# UnitB.net
KiCad netlist of a schematic drawn in Altium Designer
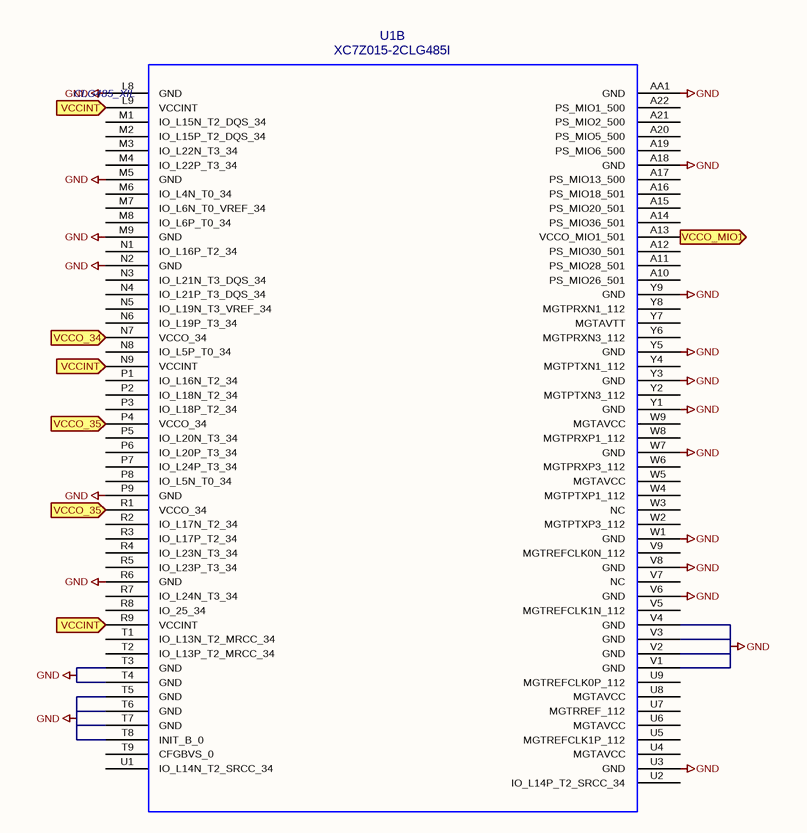
[diagram p0: UnitB.SchDoc]

(export (version "E")
  (design (tool "Eeschema 10.0.6"))
  (components
    (comp (ref "U1")
      (value "XC7Z015-2CLG485I")
      (footprint "CLG485_XIL")
      (libsource (lib "XC7Z015-CLG485") (part "XC7Z015-2CLG485I"))
    )
  )
  (nets
    (net (code "1") (name "/VCCINT") (class "Default")
      (node (ref "U1") (pin "L9") (pinfunction "VCCINT_L9") (pintype "passive"))
      (node (ref "U1") (pin "N9") (pinfunction "VCCINT_N9") (pintype "passive"))
      (node (ref "U1") (pin "R9") (pinfunction "VCCINT_R9") (pintype "passive"))
    )
    (net (code "2") (name "/VCCO_34") (class "Default")
      (node (ref "U1") (pin "N7") (pinfunction "VCCO_34_N7") (pintype "passive"))
    )
    (net (code "3") (name "/VCCO_35") (class "Default")
      (node (ref "U1") (pin "P4") (pinfunction "VCCO_34_P4") (pintype "passive"))
      (node (ref "U1") (pin "R1") (pinfunction "VCCO_34_R1") (pintype "passive"))
    )
    (net (code "4") (name "/VCCO_MIO1") (class "Default")
      (node (ref "U1") (pin "A13") (pinfunction "VCCO_MIO1_501_A13") (pintype "passive"))
    )
    (net (code "5") (name "GND") (class "Default")
      (node (ref "U1") (pin "A18") (pinfunction "GND_A18") (pintype "passive"))
      (node (ref "U1") (pin "AA1") (pinfunction "GND_AA1") (pintype "passive"))
      (node (ref "U1") (pin "L8") (pinfunction "GND_L8") (pintype "passive"))
      (node (ref "U1") (pin "M5") (pinfunction "GND_M5") (pintype "passive"))
      (node (ref "U1") (pin "M9") (pinfunction "GND_M9") (pintype "passive"))
      (node (ref "U1") (pin "N2") (pinfunction "GND_N2") (pintype "passive"))
      (node (ref "U1") (pin "P9") (pinfunction "GND_P9") (pintype "passive"))
      (node (ref "U1") (pin "R6") (pinfunction "GND_R6") (pintype "passive"))
      (node (ref "U1") (pin "T3") (pinfunction "GND_T3") (pintype "passive"))
      (node (ref "U1") (pin "T4") (pinfunction "GND_T4") (pintype "passive"))
      (node (ref "U1") (pin "T5") (pinfunction "GND_T5") (pintype "passive"))
      (node (ref "U1") (pin "T6") (pinfunction "GND_T6") (pintype "passive"))
      (node (ref "U1") (pin "T7") (pinfunction "GND_T7") (pintype "passive"))
      (node (ref "U1") (pin "T8") (pinfunction "INIT_B_0_T8") (pintype "passive"))
      (node (ref "U1") (pin "U3") (pinfunction "GND_U3") (pintype "passive"))
      (node (ref "U1") (pin "V1") (pinfunction "GND_V1") (pintype "passive"))
      (node (ref "U1") (pin "V2") (pinfunction "GND_V2") (pintype "passive"))
      (node (ref "U1") (pin "V3") (pinfunction "GND_V3") (pintype "passive"))
      (node (ref "U1") (pin "V4") (pinfunction "GND_V4") (pintype "passive"))
      (node (ref "U1") (pin "V6") (pinfunction "GND_V6") (pintype "passive"))
      (node (ref "U1") (pin "V8") (pinfunction "GND_V8") (pintype "passive"))
      (node (ref "U1") (pin "W1") (pinfunction "GND_W1") (pintype "passive"))
      (node (ref "U1") (pin "W7") (pinfunction "GND_W7") (pintype "passive"))
      (node (ref "U1") (pin "Y1") (pinfunction "GND_Y1") (pintype "passive"))
      (node (ref "U1") (pin "Y3") (pinfunction "GND_Y3") (pintype "passive"))
      (node (ref "U1") (pin "Y5") (pinfunction "GND_Y5") (pintype "passive"))
      (node (ref "U1") (pin "Y9") (pinfunction "GND_Y9") (pintype "passive"))
    )
    (net (code "6") (name "unconnected-(U1B-CFGBVS_0-PadT9)") (class "Default")
      (node (ref "U1") (pin "T9") (pinfunction "CFGBVS_0_T9") (pintype "passive"))
    )
    (net (code "7") (name "unconnected-(U1B-IO_25_34-PadR8)") (class "Default")
      (node (ref "U1") (pin "R8") (pinfunction "IO_25_34_R8") (pintype "passive"))
    )
    (net (code "8") (name "unconnected-(U1B-IO_L4N_T0_34-PadM6)") (class "Default")
      (node (ref "U1") (pin "M6") (pinfunction "IO_L4N_T0_34_M6") (pintype "passive"))
    )
    (net (code "9") (name "unconnected-(U1B-IO_L5N_T0_34-PadP8)") (class "Default")
      (node (ref "U1") (pin "P8") (pinfunction "IO_L5N_T0_34_P8") (pintype "passive"))
    )
    (net (code "10") (name "unconnected-(U1B-IO_L5P_T0_34-PadN8)") (class "Default")
      (node (ref "U1") (pin "N8") (pinfunction "IO_L5P_T0_34_N8") (pintype "passive"))
    )
    (net (code "11") (name "unconnected-(U1B-IO_L6N_T0_VREF_34-PadM7)") (class "Default")
      (node (ref "U1") (pin "M7") (pinfunction "IO_L6N_T0_VREF_34_M7") (pintype "passive"))
    )
    (net (code "12") (name "unconnected-(U1B-IO_L6P_T0_34-PadM8)") (class "Default")
      (node (ref "U1") (pin "M8") (pinfunction "IO_L6P_T0_34_M8") (pintype "passive"))
    )
    (net (code "13") (name "unconnected-(U1B-IO_L13N_T2_MRCC_34-PadT1)") (class "Default")
      (node (ref "U1") (pin "T1") (pinfunction "IO_L13N_T2_MRCC_34_T1") (pintype "passive"))
    )
    (net (code "14") (name "unconnected-(U1B-IO_L13P_T2_MRCC_34-PadT2)") (class "Default")
      (node (ref "U1") (pin "T2") (pinfunction "IO_L13P_T2_MRCC_34_T2") (pintype "passive"))
    )
    (net (code "15") (name "unconnected-(U1B-IO_L14N_T2_SRCC_34-PadU1)") (class "Default")
      (node (ref "U1") (pin "U1") (pinfunction "IO_L14N_T2_SRCC_34_U1") (pintype "passive"))
    )
    (net (code "16") (name "unconnected-(U1B-IO_L14P_T2_SRCC_34-PadU2)") (class "Default")
      (node (ref "U1") (pin "U2") (pinfunction "IO_L14P_T2_SRCC_34_U2") (pintype "passive"))
    )
    (net (code "17") (name "unconnected-(U1B-IO_L15N_T2_DQS_34-PadM1)") (class "Default")
      (node (ref "U1") (pin "M1") (pinfunction "IO_L15N_T2_DQS_34_M1") (pintype "passive"))
    )
    (net (code "18") (name "unconnected-(U1B-IO_L15P_T2_DQS_34-PadM2)") (class "Default")
      (node (ref "U1") (pin "M2") (pinfunction "IO_L15P_T2_DQS_34_M2") (pintype "passive"))
    )
    (net (code "19") (name "unconnected-(U1B-IO_L16N_T2_34-PadP1)") (class "Default")
      (node (ref "U1") (pin "P1") (pinfunction "IO_L16N_T2_34_P1") (pintype "passive"))
    )
    (net (code "20") (name "unconnected-(U1B-IO_L16P_T2_34-PadN1)") (class "Default")
      (node (ref "U1") (pin "N1") (pinfunction "IO_L16P_T2_34_N1") (pintype "passive"))
    )
    (net (code "21") (name "unconnected-(U1B-IO_L17N_T2_34-PadR2)") (class "Default")
      (node (ref "U1") (pin "R2") (pinfunction "IO_L17N_T2_34_R2") (pintype "passive"))
    )
    (net (code "22") (name "unconnected-(U1B-IO_L17P_T2_34-PadR3)") (class "Default")
      (node (ref "U1") (pin "R3") (pinfunction "IO_L17P_T2_34_R3") (pintype "passive"))
    )
    (net (code "23") (name "unconnected-(U1B-IO_L18N_T2_34-PadP2)") (class "Default")
      (node (ref "U1") (pin "P2") (pinfunction "IO_L18N_T2_34_P2") (pintype "passive"))
    )
    (net (code "24") (name "unconnected-(U1B-IO_L18P_T2_34-PadP3)") (class "Default")
      (node (ref "U1") (pin "P3") (pinfunction "IO_L18P_T2_34_P3") (pintype "passive"))
    )
    (net (code "25") (name "unconnected-(U1B-IO_L19N_T3_VREF_34-PadN5)") (class "Default")
      (node (ref "U1") (pin "N5") (pinfunction "IO_L19N_T3_VREF_34_N5") (pintype "passive"))
    )
    (net (code "26") (name "unconnected-(U1B-IO_L19P_T3_34-PadN6)") (class "Default")
      (node (ref "U1") (pin "N6") (pinfunction "IO_L19P_T3_34_N6") (pintype "passive"))
    )
    (net (code "27") (name "unconnected-(U1B-IO_L20N_T3_34-PadP5)") (class "Default")
      (node (ref "U1") (pin "P5") (pinfunction "IO_L20N_T3_34_P5") (pintype "passive"))
    )
    (net (code "28") (name "unconnected-(U1B-IO_L20P_T3_34-PadP6)") (class "Default")
      (node (ref "U1") (pin "P6") (pinfunction "IO_L20P_T3_34_P6") (pintype "passive"))
    )
    (net (code "29") (name "unconnected-(U1B-IO_L21N_T3_DQS_34-PadN3)") (class "Default")
      (node (ref "U1") (pin "N3") (pinfunction "IO_L21N_T3_DQS_34_N3") (pintype "passive"))
    )
    (net (code "30") (name "unconnected-(U1B-IO_L21P_T3_DQS_34-PadN4)") (class "Default")
      (node (ref "U1") (pin "N4") (pinfunction "IO_L21P_T3_DQS_34_N4") (pintype "passive"))
    )
    (net (code "31") (name "unconnected-(U1B-IO_L22N_T3_34-PadM3)") (class "Default")
      (node (ref "U1") (pin "M3") (pinfunction "IO_L22N_T3_34_M3") (pintype "passive"))
    )
    (net (code "32") (name "unconnected-(U1B-IO_L22P_T3_34-PadM4)") (class "Default")
      (node (ref "U1") (pin "M4") (pinfunction "IO_L22P_T3_34_M4") (pintype "passive"))
    )
    (net (code "33") (name "unconnected-(U1B-IO_L23N_T3_34-PadR4)") (class "Default")
      (node (ref "U1") (pin "R4") (pinfunction "IO_L23N_T3_34_R4") (pintype "passive"))
    )
    (net (code "34") (name "unconnected-(U1B-IO_L23P_T3_34-PadR5)") (class "Default")
      (node (ref "U1") (pin "R5") (pinfunction "IO_L23P_T3_34_R5") (pintype "passive"))
    )
    (net (code "35") (name "unconnected-(U1B-IO_L24N_T3_34-PadR7)") (class "Default")
      (node (ref "U1") (pin "R7") (pinfunction "IO_L24N_T3_34_R7") (pintype "passive"))
    )
    (net (code "36") (name "unconnected-(U1B-IO_L24P_T3_34-PadP7)") (class "Default")
      (node (ref "U1") (pin "P7") (pinfunction "IO_L24P_T3_34_P7") (pintype "passive"))
    )
    (net (code "37") (name "unconnected-(U1B-MGTAVCC-PadU4)") (class "Default")
      (node (ref "U1") (pin "U4") (pinfunction "MGTAVCC_U4") (pintype "passive"))
    )
    (net (code "38") (name "unconnected-(U1B-MGTAVCC-PadU6)") (class "Default")
      (node (ref "U1") (pin "U6") (pinfunction "MGTAVCC_U6") (pintype "passive"))
    )
    (net (code "39") (name "unconnected-(U1B-MGTAVCC-PadU8)") (class "Default")
      (node (ref "U1") (pin "U8") (pinfunction "MGTAVCC_U8") (pintype "passive"))
    )
    (net (code "40") (name "unconnected-(U1B-MGTAVCC-PadW5)") (class "Default")
      (node (ref "U1") (pin "W5") (pinfunction "MGTAVCC_W5") (pintype "passive"))
    )
    (net (code "41") (name "unconnected-(U1B-MGTAVCC-PadW9)") (class "Default")
      (node (ref "U1") (pin "W9") (pinfunction "MGTAVCC_W9") (pintype "passive"))
    )
    (net (code "42") (name "unconnected-(U1B-MGTAVTT-PadY7)") (class "Default")
      (node (ref "U1") (pin "Y7") (pinfunction "MGTAVTT_Y7") (pintype "passive"))
    )
    (net (code "43") (name "unconnected-(U1B-MGTPRXN1_112-PadY8)") (class "Default")
      (node (ref "U1") (pin "Y8") (pinfunction "MGTPRXN1_112_Y8") (pintype "passive"))
    )
    (net (code "44") (name "unconnected-(U1B-MGTPRXN3_112-PadY6)") (class "Default")
      (node (ref "U1") (pin "Y6") (pinfunction "MGTPRXN3_112_Y6") (pintype "passive"))
    )
    (net (code "45") (name "unconnected-(U1B-MGTPRXP1_112-PadW8)") (class "Default")
      (node (ref "U1") (pin "W8") (pinfunction "MGTPRXP1_112_W8") (pintype "passive"))
    )
    (net (code "46") (name "unconnected-(U1B-MGTPRXP3_112-PadW6)") (class "Default")
      (node (ref "U1") (pin "W6") (pinfunction "MGTPRXP3_112_W6") (pintype "passive"))
    )
    (net (code "47") (name "unconnected-(U1B-MGTPTXN1_112-PadY4)") (class "Default")
      (node (ref "U1") (pin "Y4") (pinfunction "MGTPTXN1_112_Y4") (pintype "passive"))
    )
    (net (code "48") (name "unconnected-(U1B-MGTPTXN3_112-PadY2)") (class "Default")
      (node (ref "U1") (pin "Y2") (pinfunction "MGTPTXN3_112_Y2") (pintype "passive"))
    )
    (net (code "49") (name "unconnected-(U1B-MGTPTXP1_112-PadW4)") (class "Default")
      (node (ref "U1") (pin "W4") (pinfunction "MGTPTXP1_112_W4") (pintype "passive"))
    )
    (net (code "50") (name "unconnected-(U1B-MGTPTXP3_112-PadW2)") (class "Default")
      (node (ref "U1") (pin "W2") (pinfunction "MGTPTXP3_112_W2") (pintype "passive"))
    )
    (net (code "51") (name "unconnected-(U1B-MGTREFCLK0N_112-PadV9)") (class "Default")
      (node (ref "U1") (pin "V9") (pinfunction "MGTREFCLK0N_112_V9") (pintype "passive"))
    )
    (net (code "52") (name "unconnected-(U1B-MGTREFCLK0P_112-PadU9)") (class "Default")
      (node (ref "U1") (pin "U9") (pinfunction "MGTREFCLK0P_112_U9") (pintype "passive"))
    )
    (net (code "53") (name "unconnected-(U1B-MGTREFCLK1N_112-PadV5)") (class "Default")
      (node (ref "U1") (pin "V5") (pinfunction "MGTREFCLK1N_112_V5") (pintype "passive"))
    )
    (net (code "54") (name "unconnected-(U1B-MGTREFCLK1P_112-PadU5)") (class "Default")
      (node (ref "U1") (pin "U5") (pinfunction "MGTREFCLK1P_112_U5") (pintype "passive"))
    )
    (net (code "55") (name "unconnected-(U1B-MGTRREF_112-PadU7)") (class "Default")
      (node (ref "U1") (pin "U7") (pinfunction "MGTRREF_112_U7") (pintype "passive"))
    )
    (net (code "56") (name "unconnected-(U1B-NC-PadV7)") (class "Default")
      (node (ref "U1") (pin "V7") (pinfunction "NC_V7") (pintype "passive"))
    )
    (net (code "57") (name "unconnected-(U1B-NC-PadW3)") (class "Default")
      (node (ref "U1") (pin "W3") (pinfunction "NC_W3") (pintype "passive"))
    )
    (net (code "58") (name "unconnected-(U1B-PS_MIO1_500-PadA22)") (class "Default")
      (node (ref "U1") (pin "A22") (pinfunction "PS_MIO1_500_A22") (pintype "passive"))
    )
    (net (code "59") (name "unconnected-(U1B-PS_MIO2_500-PadA21)") (class "Default")
      (node (ref "U1") (pin "A21") (pinfunction "PS_MIO2_500_A21") (pintype "passive"))
    )
    (net (code "60") (name "unconnected-(U1B-PS_MIO5_500-PadA20)") (class "Default")
      (node (ref "U1") (pin "A20") (pinfunction "PS_MIO5_500_A20") (pintype "passive"))
    )
    (net (code "61") (name "unconnected-(U1B-PS_MIO6_500-PadA19)") (class "Default")
      (node (ref "U1") (pin "A19") (pinfunction "PS_MIO6_500_A19") (pintype "passive"))
    )
    (net (code "62") (name "unconnected-(U1B-PS_MIO13_500-PadA17)") (class "Default")
      (node (ref "U1") (pin "A17") (pinfunction "PS_MIO13_500_A17") (pintype "passive"))
    )
    (net (code "63") (name "unconnected-(U1B-PS_MIO18_501-PadA16)") (class "Default")
      (node (ref "U1") (pin "A16") (pinfunction "PS_MIO18_501_A16") (pintype "passive"))
    )
    (net (code "64") (name "unconnected-(U1B-PS_MIO20_501-PadA15)") (class "Default")
      (node (ref "U1") (pin "A15") (pinfunction "PS_MIO20_501_A15") (pintype "passive"))
    )
    (net (code "65") (name "unconnected-(U1B-PS_MIO26_501-PadA10)") (class "Default")
      (node (ref "U1") (pin "A10") (pinfunction "PS_MIO26_501_A10") (pintype "passive"))
    )
    (net (code "66") (name "unconnected-(U1B-PS_MIO28_501-PadA11)") (class "Default")
      (node (ref "U1") (pin "A11") (pinfunction "PS_MIO28_501_A11") (pintype "passive"))
    )
    (net (code "67") (name "unconnected-(U1B-PS_MIO30_501-PadA12)") (class "Default")
      (node (ref "U1") (pin "A12") (pinfunction "PS_MIO30_501_A12") (pintype "passive"))
    )
    (net (code "68") (name "unconnected-(U1B-PS_MIO36_501-PadA14)") (class "Default")
      (node (ref "U1") (pin "A14") (pinfunction "PS_MIO36_501_A14") (pintype "passive"))
    )
  )
)
